# design.net
KiCad netlist of a schematic drawn in EAGLE
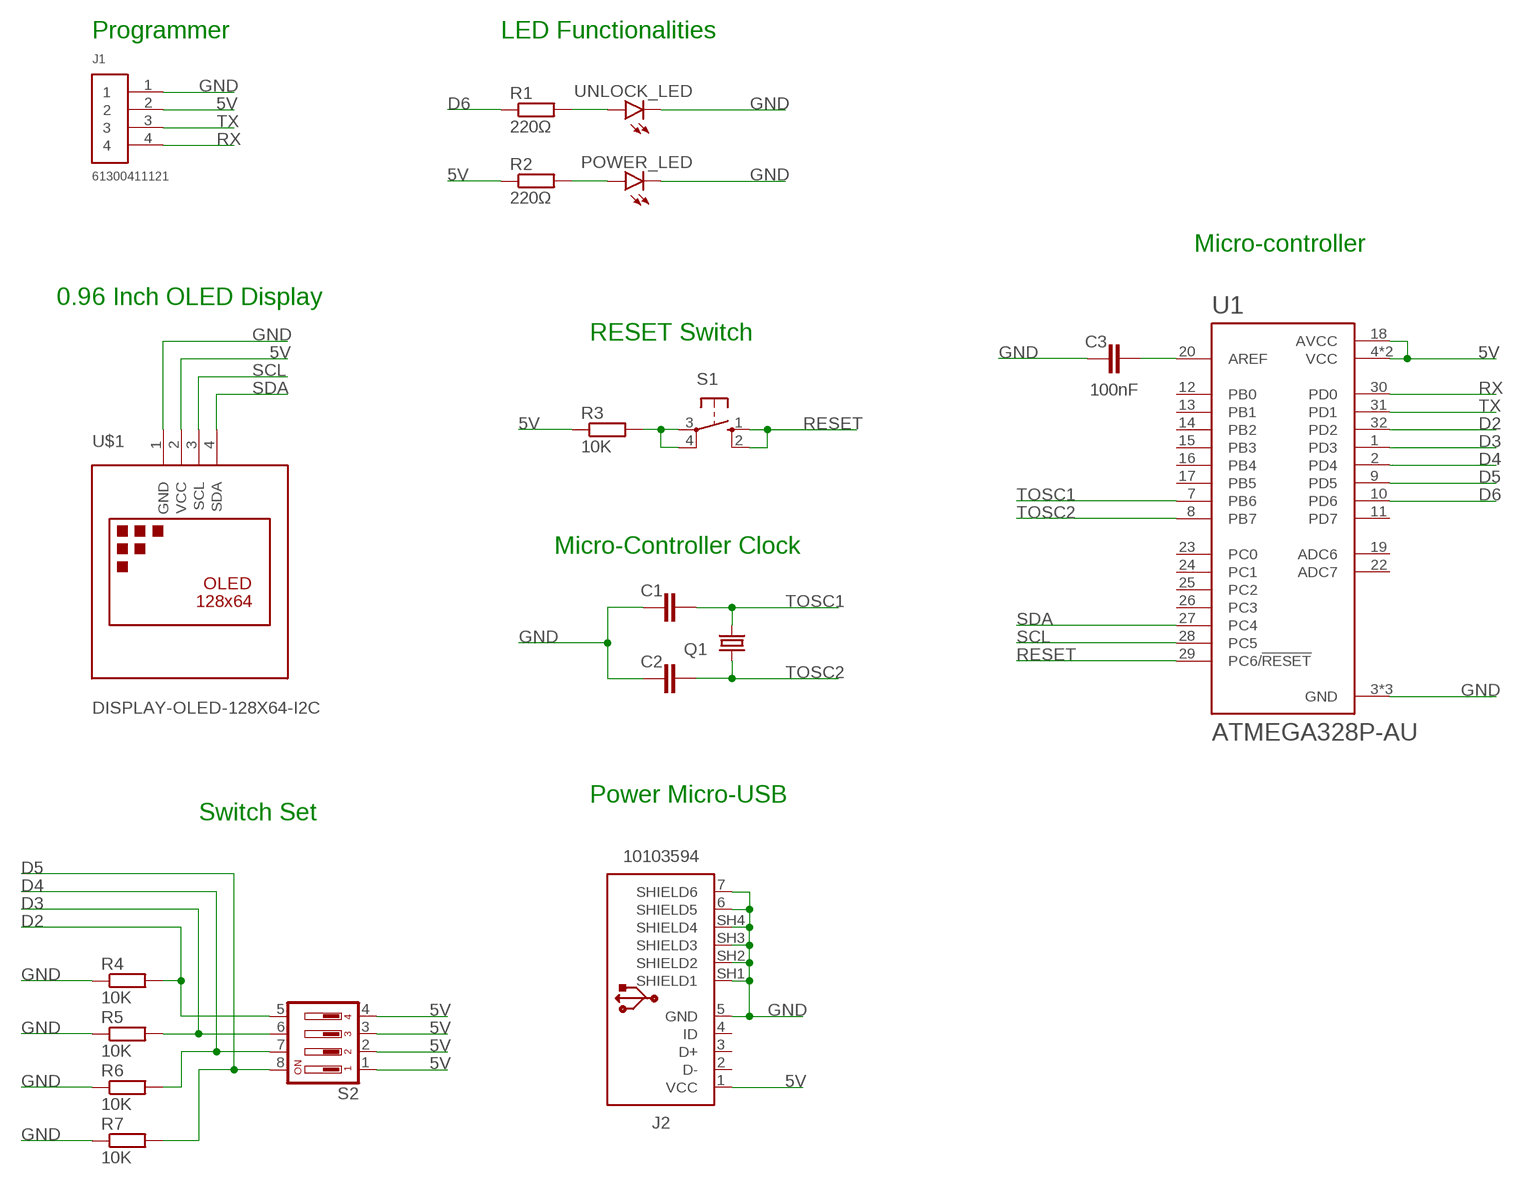
[diagram p0: schematic, sheet 1]

(export (version "E")
  (design (tool "Eeschema 10.0.6"))
  (components
    (comp (ref "C1")
      (value "C-EUC0805")
      (footprint "eagle-import:C0805")
      (libsource (lib "eagle-import") (part "C-EUC0805"))
    )
    (comp (ref "C2")
      (value "C-EUC0805")
      (footprint "eagle-import:C0805")
      (libsource (lib "eagle-import") (part "C-EUC0805"))
    )
    (comp (ref "C3")
      (value "100nF")
      (footprint "eagle-import:C0805")
      (libsource (lib "eagle-import") (part "C-EUC0805"))
    )
    (comp (ref "J1")
      (value "61300411121")
      (footprint "eagle-import:61300411121")
      (fields
        (field (name "DIGI_KEY_PART_NUMBER") "732-5317-ND")
        (field (name "MANUFACTURER") "Wurth Electronics Inc.")
        (field (name "CREATED_BY") "PCBLayout.com")
      )
      (libsource (lib "eagle-import") (part "61300411121"))
    )
    (comp (ref "J2")
      (value "10103594")
      (footprint "eagle-import:10103594")
      (fields (field (name "MANUFACTURER") "Amphenol ICC (FCI)") (field (name "MPN") "10103594-0001LF"))
      (libsource (lib "eagle-import") (part "10103594"))
    )
    (comp (ref "POWER_LED")
      (value "LEDCHIP-LED0805")
      (footprint "eagle-import:CHIP-LED0805")
      (libsource (lib "eagle-import") (part "LEDCHIP-LED0805"))
    )
    (comp (ref "Q1")
      (value "CRYSTALHC49U-V")
      (footprint "eagle-import:HC49U-V")
      (libsource (lib "eagle-import") (part "CRYSTALHC49U-V"))
    )
    (comp (ref "R1")
      (value "220Ω")
      (footprint "eagle-import:R0805")
      (libsource (lib "eagle-import") (part "R-EU_R0805"))
    )
    (comp (ref "R2")
      (value "220Ω")
      (footprint "eagle-import:R0805")
      (libsource (lib "eagle-import") (part "R-EU_R0805"))
    )
    (comp (ref "R3")
      (value "10K")
      (footprint "eagle-import:R0805")
      (libsource (lib "eagle-import") (part "R-EU_R0805"))
    )
    (comp (ref "R4")
      (value "10K")
      (footprint "eagle-import:R0805")
      (libsource (lib "eagle-import") (part "R-EU_R0805"))
    )
    (comp (ref "R5")
      (value "10K")
      (footprint "eagle-import:R0805")
      (libsource (lib "eagle-import") (part "R-EU_R0805"))
    )
    (comp (ref "R6")
      (value "10K")
      (footprint "eagle-import:R0805")
      (libsource (lib "eagle-import") (part "R-EU_R0805"))
    )
    (comp (ref "R7")
      (value "10K")
      (footprint "eagle-import:R0805")
      (libsource (lib "eagle-import") (part "R-EU_R0805"))
    )
    (comp (ref "S1")
      (value "10-XX")
      (footprint "eagle-import:B3F-10XX")
      (fields (field (name "MPN") "B3F-1000"))
      (libsource (lib "eagle-import") (part "10-XX"))
    )
    (comp (ref "S2")
      (value "DA04")
      (footprint "eagle-import:DA-04")
      (fields (field (name "MPN") "MCDA04"))
      (libsource (lib "eagle-import") (part "DA04"))
    )
    (comp (ref "U$1")
      (value "DISPLAY-OLED-128X64-I2C")
      (footprint "eagle-import:DISPLAY-OLED-128X64-I2C")
      (libsource (lib "eagle-import") (part "DISPLAY-OLED-128X64-I2C"))
    )
    (comp (ref "U1")
      (value "ATMEGA328P-AU")
      (footprint "eagle-import:QFP80P900X900X120-32N")
      (fields (field (name "MF") "Microchip Technology"))
      (libsource (lib "eagle-import") (part "ATMEGA328P-AU"))
    )
    (comp (ref "UNLOCK_LED")
      (value "LEDCHIP-LED0805")
      (footprint "eagle-import:CHIP-LED0805")
      (libsource (lib "eagle-import") (part "LEDCHIP-LED0805"))
    )
  )
  (nets
    (net (code "1") (name "/5V") (class "Default")
      (node (ref "J1") (pin "2") (pinfunction "2_2") (pintype "passive"))
      (node (ref "J2") (pin "1") (pinfunction "VCC_1") (pintype "power_in"))
      (node (ref "R2") (pin "1") (pinfunction "1_1") (pintype "passive"))
      (node (ref "R3") (pin "1") (pinfunction "1_1") (pintype "passive"))
      (node (ref "S2") (pin "1") (pinfunction "1_1") (pintype "passive"))
      (node (ref "S2") (pin "2") (pinfunction "2_2") (pintype "passive"))
      (node (ref "S2") (pin "3") (pinfunction "3_3") (pintype "passive"))
      (node (ref "S2") (pin "4") (pinfunction "4_4") (pintype "passive"))
      (node (ref "U$1") (pin "2") (pinfunction "VCC_2") (pintype "power_in"))
      (node (ref "U1") (pin "18") (pinfunction "AVCC_18") (pintype "power_in"))
      (node (ref "U1") (pin "4") (pinfunction "VCC_4") (pintype "power_in"))
      (node (ref "U1") (pin "6") (pinfunction "VCC_6") (pintype "power_in"))
    )
    (net (code "2") (name "/D2") (class "Default")
      (node (ref "R4") (pin "2") (pinfunction "2_2") (pintype "passive"))
      (node (ref "S2") (pin "5") (pinfunction "5_5") (pintype "passive"))
      (node (ref "U1") (pin "32") (pinfunction "PD2_32") (pintype "bidirectional"))
    )
    (net (code "3") (name "/D3") (class "Default")
      (node (ref "R5") (pin "2") (pinfunction "2_2") (pintype "passive"))
      (node (ref "S2") (pin "6") (pinfunction "6_6") (pintype "passive"))
      (node (ref "U1") (pin "1") (pinfunction "PD3_1") (pintype "bidirectional"))
    )
    (net (code "4") (name "/D4") (class "Default")
      (node (ref "R6") (pin "2") (pinfunction "2_2") (pintype "passive"))
      (node (ref "S2") (pin "7") (pinfunction "7_7") (pintype "passive"))
      (node (ref "U1") (pin "2") (pinfunction "PD4_2") (pintype "bidirectional"))
    )
    (net (code "5") (name "/D5") (class "Default")
      (node (ref "R7") (pin "2") (pinfunction "2_2") (pintype "passive"))
      (node (ref "S2") (pin "8") (pinfunction "8_8") (pintype "passive"))
      (node (ref "U1") (pin "9") (pinfunction "PD5_9") (pintype "bidirectional"))
    )
    (net (code "6") (name "/D6") (class "Default")
      (node (ref "R1") (pin "1") (pinfunction "1_1") (pintype "passive"))
      (node (ref "U1") (pin "10") (pinfunction "PD6_10") (pintype "bidirectional"))
    )
    (net (code "7") (name "/GND") (class "Default")
      (node (ref "C1") (pin "1") (pinfunction "1_1") (pintype "passive"))
      (node (ref "C2") (pin "1") (pinfunction "1_1") (pintype "passive"))
      (node (ref "C3") (pin "1") (pinfunction "1_1") (pintype "passive"))
      (node (ref "J1") (pin "1") (pinfunction "1_1") (pintype "passive"))
      (node (ref "J2") (pin "5") (pinfunction "GND_5") (pintype "power_in"))
      (node (ref "J2") (pin "6") (pinfunction "SHIELD5_6") (pintype "power_in"))
      (node (ref "J2") (pin "7") (pinfunction "SHIELD6_7") (pintype "power_in"))
      (node (ref "J2") (pin "SH1") (pinfunction "SHIELD1_SH1") (pintype "power_in"))
      (node (ref "J2") (pin "SH2") (pinfunction "SHIELD2_SH2") (pintype "power_in"))
      (node (ref "J2") (pin "SH3") (pinfunction "SHIELD3_SH3") (pintype "power_in"))
      (node (ref "J2") (pin "SH4") (pinfunction "SHIELD4_SH4") (pintype "power_in"))
      (node (ref "POWER_LED") (pin "C") (pinfunction "C_C") (pintype "passive"))
      (node (ref "R4") (pin "1") (pinfunction "1_1") (pintype "passive"))
      (node (ref "R5") (pin "1") (pinfunction "1_1") (pintype "passive"))
      (node (ref "R6") (pin "1") (pinfunction "1_1") (pintype "passive"))
      (node (ref "R7") (pin "1") (pinfunction "1_1") (pintype "passive"))
      (node (ref "U$1") (pin "1") (pinfunction "GND_1") (pintype "power_in"))
      (node (ref "U1") (pin "21") (pinfunction "GND_21") (pintype "power_in"))
      (node (ref "U1") (pin "3") (pinfunction "GND_3") (pintype "power_in"))
      (node (ref "U1") (pin "5") (pinfunction "GND_5") (pintype "power_in"))
      (node (ref "UNLOCK_LED") (pin "C") (pinfunction "C_C") (pintype "passive"))
    )
    (net (code "8") (name "/RESET") (class "Default")
      (node (ref "S1") (pin "1") (pinfunction "S_1") (pintype "passive"))
      (node (ref "S1") (pin "2") (pinfunction "S1_2") (pintype "passive"))
      (node (ref "U1") (pin "29") (pinfunction "PC6/~{RESET}_29") (pintype "bidirectional"))
    )
    (net (code "9") (name "/RX") (class "Default")
      (node (ref "J1") (pin "4") (pinfunction "4_4") (pintype "passive"))
      (node (ref "U1") (pin "30") (pinfunction "PD0_30") (pintype "bidirectional"))
    )
    (net (code "10") (name "/SCL") (class "Default")
      (node (ref "U$1") (pin "3") (pinfunction "SCL_3") (pintype "bidirectional"))
      (node (ref "U1") (pin "28") (pinfunction "PC5_28") (pintype "bidirectional"))
    )
    (net (code "11") (name "/SDA") (class "Default")
      (node (ref "U$1") (pin "4") (pinfunction "SDA_4") (pintype "bidirectional"))
      (node (ref "U1") (pin "27") (pinfunction "PC4_27") (pintype "bidirectional"))
    )
    (net (code "12") (name "/TOSC1") (class "Default")
      (node (ref "C1") (pin "2") (pinfunction "2_2") (pintype "passive"))
      (node (ref "Q1") (pin "2") (pinfunction "2_2") (pintype "passive"))
      (node (ref "U1") (pin "7") (pinfunction "PB6_7") (pintype "bidirectional"))
    )
    (net (code "13") (name "/TOSC2") (class "Default")
      (node (ref "C2") (pin "2") (pinfunction "2_2") (pintype "passive"))
      (node (ref "Q1") (pin "1") (pinfunction "1_1") (pintype "passive"))
      (node (ref "U1") (pin "8") (pinfunction "PB7_8") (pintype "bidirectional"))
    )
    (net (code "14") (name "/TX") (class "Default")
      (node (ref "J1") (pin "3") (pinfunction "3_3") (pintype "passive"))
      (node (ref "U1") (pin "31") (pinfunction "PD1_31") (pintype "bidirectional"))
    )
    (net (code "15") (name "Net-(POWER_LED-PadA)") (class "Default")
      (node (ref "POWER_LED") (pin "A") (pinfunction "A_A") (pintype "passive"))
      (node (ref "R2") (pin "2") (pinfunction "2_2") (pintype "passive"))
    )
    (net (code "16") (name "Net-(R1-Pad2)") (class "Default")
      (node (ref "R1") (pin "2") (pinfunction "2_2") (pintype "passive"))
      (node (ref "UNLOCK_LED") (pin "A") (pinfunction "A_A") (pintype "passive"))
    )
    (net (code "17") (name "Net-(S1-P)") (class "Default")
      (node (ref "R3") (pin "2") (pinfunction "2_2") (pintype "passive"))
      (node (ref "S1") (pin "3") (pinfunction "P_3") (pintype "passive"))
      (node (ref "S1") (pin "4") (pinfunction "P1_4") (pintype "passive"))
    )
    (net (code "18") (name "Net-(U1-AREF)") (class "Default")
      (node (ref "C3") (pin "2") (pinfunction "2_2") (pintype "passive"))
      (node (ref "U1") (pin "20") (pinfunction "AREF_20") (pintype "input"))
    )
    (net (code "19") (name "unconnected-(J2-D+-Pad3)") (class "Default")
      (node (ref "J2") (pin "3") (pinfunction "D+_3") (pintype "bidirectional"))
    )
    (net (code "20") (name "unconnected-(J2-D--Pad2)") (class "Default")
      (node (ref "J2") (pin "2") (pinfunction "D-_2") (pintype "bidirectional"))
    )
    (net (code "21") (name "unconnected-(J2-ID-Pad4)") (class "Default")
      (node (ref "J2") (pin "4") (pinfunction "ID_4") (pintype "bidirectional"))
    )
    (net (code "22") (name "unconnected-(U1-ADC6-Pad19)") (class "Default")
      (node (ref "U1") (pin "19") (pinfunction "ADC6_19") (pintype "bidirectional"))
    )
    (net (code "23") (name "unconnected-(U1-ADC7-Pad22)") (class "Default")
      (node (ref "U1") (pin "22") (pinfunction "ADC7_22") (pintype "bidirectional"))
    )
    (net (code "24") (name "unconnected-(U1-PB0-Pad12)") (class "Default")
      (node (ref "U1") (pin "12") (pinfunction "PB0_12") (pintype "bidirectional"))
    )
    (net (code "25") (name "unconnected-(U1-PB1-Pad13)") (class "Default")
      (node (ref "U1") (pin "13") (pinfunction "PB1_13") (pintype "bidirectional"))
    )
    (net (code "26") (name "unconnected-(U1-PB2-Pad14)") (class "Default")
      (node (ref "U1") (pin "14") (pinfunction "PB2_14") (pintype "bidirectional"))
    )
    (net (code "27") (name "unconnected-(U1-PB3-Pad15)") (class "Default")
      (node (ref "U1") (pin "15") (pinfunction "PB3_15") (pintype "bidirectional"))
    )
    (net (code "28") (name "unconnected-(U1-PB4-Pad16)") (class "Default")
      (node (ref "U1") (pin "16") (pinfunction "PB4_16") (pintype "bidirectional"))
    )
    (net (code "29") (name "unconnected-(U1-PB5-Pad17)") (class "Default")
      (node (ref "U1") (pin "17") (pinfunction "PB5_17") (pintype "bidirectional"))
    )
    (net (code "30") (name "unconnected-(U1-PC0-Pad23)") (class "Default")
      (node (ref "U1") (pin "23") (pinfunction "PC0_23") (pintype "bidirectional"))
    )
    (net (code "31") (name "unconnected-(U1-PC1-Pad24)") (class "Default")
      (node (ref "U1") (pin "24") (pinfunction "PC1_24") (pintype "bidirectional"))
    )
    (net (code "32") (name "unconnected-(U1-PC2-Pad25)") (class "Default")
      (node (ref "U1") (pin "25") (pinfunction "PC2_25") (pintype "bidirectional"))
    )
    (net (code "33") (name "unconnected-(U1-PC3-Pad26)") (class "Default")
      (node (ref "U1") (pin "26") (pinfunction "PC3_26") (pintype "bidirectional"))
    )
    (net (code "34") (name "unconnected-(U1-PD7-Pad11)") (class "Default")
      (node (ref "U1") (pin "11") (pinfunction "PD7_11") (pintype "bidirectional"))
    )
  )
)
